# Power.net
KiCad netlist of a schematic drawn in Altium Designer
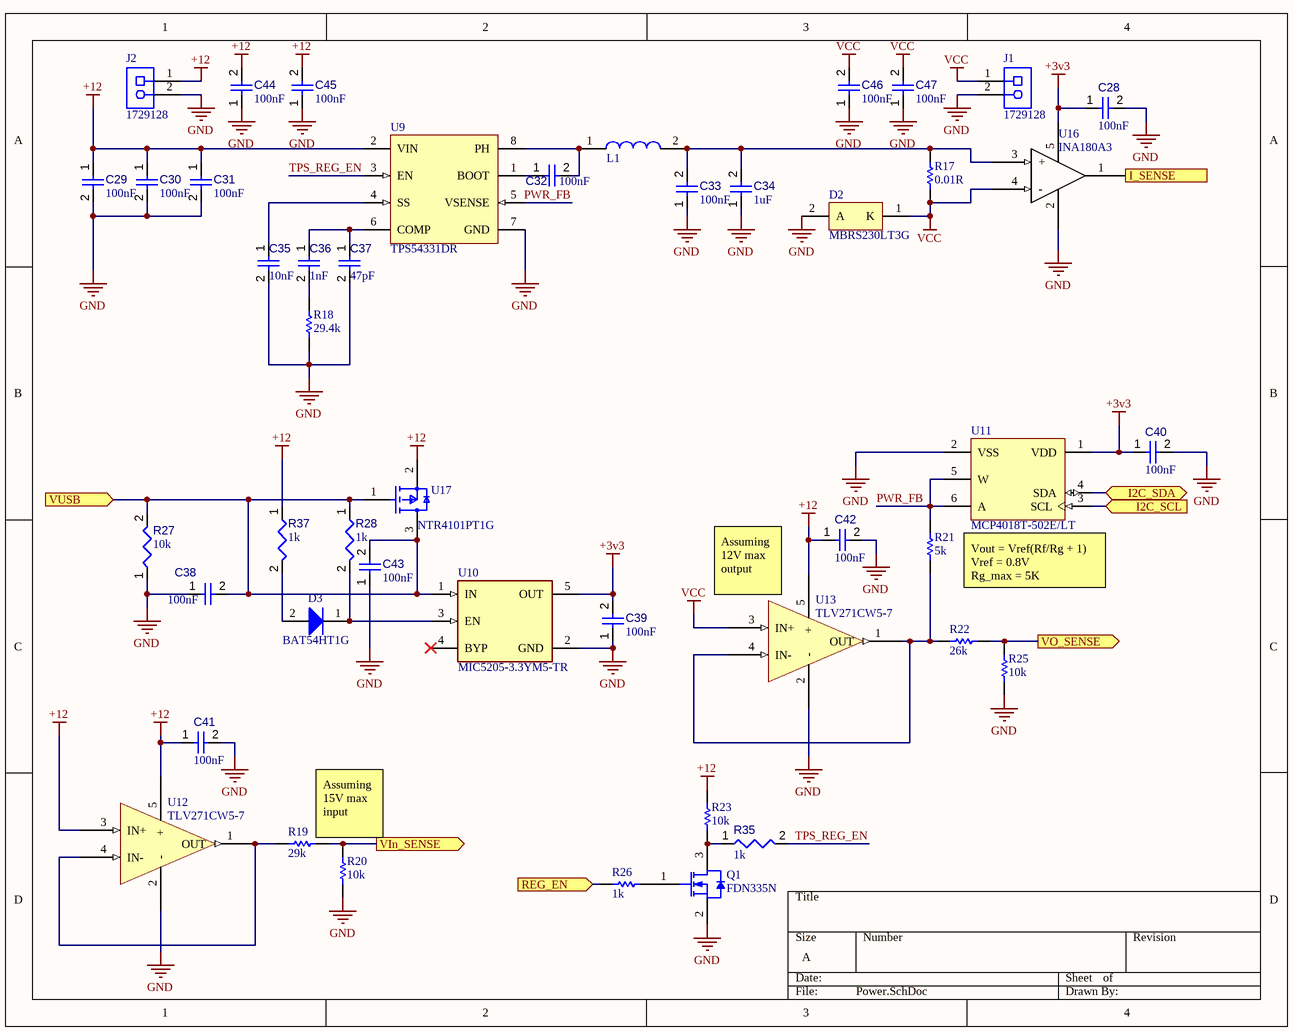
[diagram p0: Power.SchDoc]

(export (version "E")
  (design (tool "Eeschema 10.0.6"))
  (components
    (comp (ref "C28")
      (value "100nF")
      (footprint "CAPC2013X95X50ML10T25")
      (description "Chip Capacitor, 100 nF, +/- 10%, 50 V, 0805 (2012 Metric)")
      (fields (field (name "TOLERANCE") "10%") (field (name "Comment") "Capacitor 100 nF +/-10% 50 V 0805"))
      (libsource (lib "Aditya Sehgal") (part "CAP-NP-2"))
    )
    (comp (ref "C29")
      (value "100nF")
      (footprint "CAPC2013X95X50ML10T25")
      (description "Chip Capacitor, 100 nF, +/- 10%, 50 V, 0805 (2012 Metric)")
      (fields (field (name "TOLERANCE") "10%") (field (name "Comment") "Capacitor 100 nF +/-10% 50 V 0805"))
      (libsource (lib "Aditya Sehgal") (part "CAP-NP-2"))
    )
    (comp (ref "C30")
      (value "100nF")
      (footprint "CAPC2013X95X50ML10T25")
      (description "Chip Capacitor, 100 nF, +/- 10%, 50 V, 0805 (2012 Metric)")
      (fields (field (name "TOLERANCE") "10%") (field (name "Comment") "Capacitor 100 nF +/-10% 50 V 0805"))
      (libsource (lib "Aditya Sehgal") (part "CAP-NP-2"))
    )
    (comp (ref "C31")
      (value "100nF")
      (footprint "CAPC2013X95X50ML10T25")
      (description "Chip Capacitor, 100 nF, +/- 10%, 50 V, 0805 (2012 Metric)")
      (fields (field (name "TOLERANCE") "10%") (field (name "Comment") "Capacitor 100 nF +/-10% 50 V 0805"))
      (libsource (lib "Aditya Sehgal") (part "CAP-NP-2"))
    )
    (comp (ref "C32")
      (value "100nF")
      (footprint "CAPC2013X95X50ML10T25")
      (description "Chip Capacitor, 100 nF, +/- 10%, 50 V, 0805 (2012 Metric)")
      (fields (field (name "TOLERANCE") "10%") (field (name "Comment") "Capacitor 100 nF +/-10% 50 V 0805"))
      (libsource (lib "Aditya Sehgal") (part "CAP-NP-2"))
    )
    (comp (ref "C33")
      (value "100nF")
      (footprint "CAPC2013X95X50ML10T25")
      (description "Chip Capacitor, 100 nF, +/- 10%, 50 V, 0805 (2012 Metric)")
      (fields (field (name "TOLERANCE") "10%") (field (name "Comment") "Capacitor 100 nF +/-10% 50 V 0805"))
      (libsource (lib "Aditya Sehgal") (part "CAP-NP-2"))
    )
    (comp (ref "C34")
      (value "1uF")
      (footprint "CAPC2013X95X50ML10T25")
      (description "Chip Capacitor, 100 nF, +/- 10%, 50 V, 0805 (2012 Metric)")
      (fields (field (name "TOLERANCE") "10%") (field (name "Comment") "Capacitor 100 nF +/-10% 50 V 0805"))
      (libsource (lib "Aditya Sehgal") (part "CAP-NP-2"))
    )
    (comp (ref "C35")
      (value "10nF")
      (footprint "CAPC2013X95X50ML10T25")
      (description "Chip Capacitor, 100 nF, +/- 10%, 50 V, 0805 (2012 Metric)")
      (fields (field (name "TOLERANCE") "10%") (field (name "Comment") "Capacitor 100 nF +/-10% 50 V 0805"))
      (libsource (lib "Aditya Sehgal") (part "CAP-NP-2"))
    )
    (comp (ref "C36")
      (value "1nF")
      (footprint "CAPC2013X95X50ML10T25")
      (description "Chip Capacitor, 100 nF, +/- 10%, 50 V, 0805 (2012 Metric)")
      (fields (field (name "TOLERANCE") "10%") (field (name "Comment") "Capacitor 100 nF +/-10% 50 V 0805"))
      (libsource (lib "Aditya Sehgal") (part "CAP-NP-2"))
    )
    (comp (ref "C37")
      (value "47pF")
      (footprint "CAPC2013X95X50ML10T25")
      (description "Chip Capacitor, 100 nF, +/- 10%, 50 V, 0805 (2012 Metric)")
      (fields (field (name "TOLERANCE") "10%") (field (name "Comment") "Capacitor 100 nF +/-10% 50 V 0805"))
      (libsource (lib "Aditya Sehgal") (part "CAP-NP-2"))
    )
    (comp (ref "C38")
      (value "100nF")
      (footprint "CAPC2013X95X50ML10T25")
      (description "Chip Capacitor, 100 nF, +/- 10%, 50 V, 0805 (2012 Metric)")
      (fields (field (name "TOLERANCE") "10%") (field (name "Comment") "Capacitor 100 nF +/-10% 50 V 0805"))
      (libsource (lib "Aditya Sehgal") (part "CAP-NP-2"))
    )
    (comp (ref "C39")
      (value "100nF")
      (footprint "CAPC2013X95X50ML10T25")
      (description "Chip Capacitor, 100 nF, +/- 10%, 50 V, 0805 (2012 Metric)")
      (fields (field (name "TOLERANCE") "10%") (field (name "Comment") "Capacitor 100 nF +/-10% 50 V 0805"))
      (libsource (lib "Aditya Sehgal") (part "CAP-NP-2"))
    )
    (comp (ref "C40")
      (value "100nF")
      (footprint "CAPC2013X95X50ML10T25")
      (description "Chip Capacitor, 100 nF, +/- 10%, 50 V, 0805 (2012 Metric)")
      (fields (field (name "TOLERANCE") "10%") (field (name "Comment") "Capacitor 100 nF +/-10% 50 V 0805"))
      (libsource (lib "Aditya Sehgal") (part "CAP-NP-2"))
    )
    (comp (ref "C41")
      (value "100nF")
      (footprint "CAPC2013X95X50ML10T25")
      (description "Chip Capacitor, 100 nF, +/- 10%, 50 V, 0805 (2012 Metric)")
      (fields (field (name "TOLERANCE") "10%") (field (name "Comment") "Capacitor 100 nF +/-10% 50 V 0805"))
      (libsource (lib "Aditya Sehgal") (part "CAP-NP-2"))
    )
    (comp (ref "C42")
      (value "100nF")
      (footprint "CAPC2013X95X50ML10T25")
      (description "Chip Capacitor, 100 nF, +/- 10%, 50 V, 0805 (2012 Metric)")
      (fields (field (name "TOLERANCE") "10%") (field (name "Comment") "Capacitor 100 nF +/-10% 50 V 0805"))
      (libsource (lib "Aditya Sehgal") (part "CAP-NP-2"))
    )
    (comp (ref "C43")
      (value "100nF")
      (footprint "CAPC0805(2012)145_L")
      (description "Chip Capacitor, 100µF +/-20%, 6.3V, 0805, Thickness 1.45 mm")
      (fields (field (name "TOLERANCE") "10%") (field (name "Comment") "Capacitor 100µF +/-20% 6.3V 0805"))
      (libsource (lib "University of California Santa Cruz") (part "CAP-NP-2"))
    )
    (comp (ref "C44")
      (value "100nF")
      (footprint "CAPC2013X95X50LL10T25")
      (description "Chip Capacitor, 100 nF, +/- 10%, 50 V, 0805 (2012 Metric)")
      (fields (field (name "TOLERANCE") "10%") (field (name "Comment") "Capacitor 100 nF +/-10% 50 V 0805"))
      (libsource (lib "University of California Santa Cruz") (part "CAP-NP-2"))
    )
    (comp (ref "C45")
      (value "100nF")
      (footprint "CAPC2013X95X50LL10T25")
      (description "Chip Capacitor, 100 nF, +/- 10%, 50 V, 0805 (2012 Metric)")
      (fields (field (name "TOLERANCE") "10%") (field (name "Comment") "Capacitor 100 nF +/-10% 50 V 0805"))
      (libsource (lib "University of California Santa Cruz") (part "CAP-NP-2"))
    )
    (comp (ref "C46")
      (value "100nF")
      (footprint "CAPC2013X95X50LL10T25")
      (description "Chip Capacitor, 100 nF, +/- 10%, 50 V, 0805 (2012 Metric)")
      (fields (field (name "TOLERANCE") "10%") (field (name "Comment") "Capacitor 100 nF +/-10% 50 V 0805"))
      (libsource (lib "University of California Santa Cruz") (part "CAP-NP-2"))
    )
    (comp (ref "C47")
      (value "100nF")
      (footprint "CAPC2013X95X50LL10T25")
      (description "Chip Capacitor, 100 nF, +/- 10%, 50 V, 0805 (2012 Metric)")
      (fields (field (name "TOLERANCE") "10%") (field (name "Comment") "Capacitor 100 nF +/-10% 50 V 0805"))
      (libsource (lib "University of California Santa Cruz") (part "CAP-NP-2"))
    )
    (comp (ref "D2")
      (value "MBRS230LT3G")
      (footprint "ONSC-SMB-2-403A-03_D_V")
      (description "Schottky Power Rectifier, 2-Pin SMB, Pb-Free, Tape and Reel")
      (fields (field (name "MANUFACTURER") "On Semiconductor"))
      (libsource (lib "Altium Content Vault") (part "ONSC-D-K1A2-2_A"))
    )
    (comp (ref "D3")
      (value "BAT54HT1G")
      (footprint "ONSC-SOD-323-2-477-02_V")
      (description "Schottky Barrier Diode, 2-Pin SOD-323, Pb-Free, Tape and Reel")
      (fields (field (name "MANUFACTURER") "On Semiconductor"))
      (libsource (lib "Altium Content Vault") (part "ONSC-D-K1A2-2"))
    )
    (comp (ref "J1")
      (value "1729128")
      (footprint "PHOE-1729128-2_V")
      (description "PCB Terminal Block, 13.5 A, 400 V, 2-Pin THD, RoHS, Bulk")
      (fields (field (name "MANUFACTURER") "Phoenix Contact"))
      (libsource (lib "") (part "CN-2P-F-R2_1"))
    )
    (comp (ref "J2")
      (value "1729128")
      (footprint "PHOE-1729128-2_V")
      (description "PCB Terminal Block, 13.5 A, 400 V, 2-Pin THD, RoHS, Bulk")
      (fields (field (name "MANUFACTURER") "Phoenix Contact"))
      (libsource (lib "Altium Content Vault") (part "CN-2P-F-R2"))
    )
    (comp (ref "L1")
      (value "LQH5BPN4R7NT0L")
      (footprint "LQH5BPN4R7NT0L-Footprint-1")
      (description "4.7uH 2A 58mOhm 5x5mm inductor Murata")
      (libsource (lib "Aditya Sehgal") (part "LQH5BPN4R7NT0L"))
    )
    (comp (ref "Q1")
      (value "FDN335N")
      (footprint "FAIR-SSOT3L-3_V")
      (fields (field (name "MANUFACTURER") "FairchildSemiconductor"))
      (libsource (lib "Altium Content Vault") (part "NEMOS-GSD-3"))
    )
    (comp (ref "R17")
      (value "0.01R")
      (footprint "RESC3216X60X45ML15T20")
      (description "Chip Resistor, 0 Ohm, +/- 5%, 0.25 W, -55 to 155 degC, 1206 (3216 Metric)")
      (fields (field (name "POWER") "250mW") (field (name "TOLERANCE") "5%"))
      (libsource (lib "Aditya Sehgal") (part "RES-2"))
    )
    (comp (ref "R18")
      (value "29.4k")
      (footprint "RESC2013X50X35ML15T15")
      (description "Chip Resistor, 0 Ohm, +/- 1%, 125 mW, -55 to 155 degC, 0805 (2012 Metric)")
      (fields (field (name "TOLERANCE") "1%") (field (name "POWER") "125mW"))
      (libsource (lib "Aditya Sehgal") (part "RES-2"))
    )
    (comp (ref "R19")
      (value "29k")
      (footprint "RESC2013X50X35ML15T15")
      (description "Chip Resistor, 0 Ohm, +/- 1%, 125 mW, -55 to 155 degC, 0805 (2012 Metric)")
      (fields (field (name "TOLERANCE") "1%") (field (name "POWER") "125mW"))
      (libsource (lib "Aditya Sehgal") (part "RES-2"))
    )
    (comp (ref "R20")
      (value "10k")
      (footprint "RESC2013X50X35ML15T15")
      (description "Chip Resistor, 0 Ohm, +/- 1%, 125 mW, -55 to 155 degC, 0805 (2012 Metric)")
      (fields (field (name "TOLERANCE") "1%") (field (name "POWER") "125mW"))
      (libsource (lib "Aditya Sehgal") (part "RES-2"))
    )
    (comp (ref "R21")
      (value "5k")
      (footprint "RESC2013X50X35ML15T15")
      (description "Chip Resistor, 0 Ohm, +/- 1%, 125 mW, -55 to 155 degC, 0805 (2012 Metric)")
      (fields (field (name "TOLERANCE") "1%") (field (name "POWER") "125mW"))
      (libsource (lib "Aditya Sehgal") (part "RES-2"))
    )
    (comp (ref "R22")
      (value "26k")
      (footprint "RESC2013X50X35ML15T15")
      (description "Chip Resistor, 0 Ohm, +/- 1%, 125 mW, -55 to 155 degC, 0805 (2012 Metric)")
      (fields (field (name "TOLERANCE") "1%") (field (name "POWER") "125mW"))
      (libsource (lib "Aditya Sehgal") (part "RES-2"))
    )
    (comp (ref "R23")
      (value "10k")
      (footprint "RESC2013X50X35ML15T15")
      (description "Chip Resistor, 0 Ohm, +/- 1%, 125 mW, -55 to 155 degC, 0805 (2012 Metric)")
      (fields (field (name "TOLERANCE") "1%") (field (name "POWER") "125mW"))
      (libsource (lib "Aditya Sehgal") (part "RES-2"))
    )
    (comp (ref "R25")
      (value "10k")
      (footprint "RESC2013X50X35ML15T15")
      (description "Chip Resistor, 0 Ohm, +/- 1%, 125 mW, -55 to 155 degC, 0805 (2012 Metric)")
      (fields (field (name "TOLERANCE") "1%") (field (name "POWER") "125mW"))
      (libsource (lib "Aditya Sehgal") (part "RES-2"))
    )
    (comp (ref "R26")
      (value "1k")
      (footprint "RESC2013X50X35ML15T15")
      (description "Chip Resistor, 0 Ohm, +/- 1%, 125 mW, -55 to 155 degC, 0805 (2012 Metric)")
      (fields (field (name "TOLERANCE") "1%") (field (name "POWER") "125mW"))
      (libsource (lib "Aditya Sehgal") (part "RES-2"))
    )
    (comp (ref "R27")
      (value "10k")
      (footprint "RESC2013X50X35ML15T15")
      (description "Chip Resistor, 10 KOhm, +/- 1%, 125 mW, -55 to 155 degC, 0805 (2012 Metric)")
      (fields (field (name "POWER") "125mW") (field (name "TOLERANCE") "1%"))
      (libsource (lib "University of California Santa Cruz") (part "RES-2"))
    )
    (comp (ref "R28")
      (value "1k")
      (footprint "RESC2013X50X35ML15T15")
      (description "Chip Resistor, 10 KOhm, +/- 1%, 125 mW, -55 to 155 degC, 0805 (2012 Metric)")
      (fields (field (name "POWER") "125mW") (field (name "TOLERANCE") "1%"))
      (libsource (lib "University of California Santa Cruz") (part "RES-2"))
    )
    (comp (ref "R35")
      (value "1k")
      (footprint "RESC2013X50X35ML15T15")
      (description "Chip Resistor, 10 KOhm, +/- 1%, 125 mW, -55 to 155 degC, 0805 (2012 Metric)")
      (fields (field (name "POWER") "125mW") (field (name "TOLERANCE") "1%"))
      (libsource (lib "University of California Santa Cruz") (part "RES-2"))
    )
    (comp (ref "R37")
      (value "1k")
      (footprint "RESC2013X50X35ML15T15")
      (description "Chip Resistor, 10 KOhm, +/- 1%, 125 mW, -55 to 155 degC, 0805 (2012 Metric)")
      (fields (field (name "POWER") "125mW") (field (name "TOLERANCE") "1%"))
      (libsource (lib "University of California Santa Cruz") (part "RES-2"))
    )
    (comp (ref "U9")
      (value "TPS54331DR")
      (footprint "D0008A_L")
      (fields (field (name "MANUFACTURER") "Texas Instruments"))
      (libsource (lib "Altium Content Vault") (part "TI-TPS54331D8"))
    )
    (comp (ref "U10")
      (value "MIC5205-3.3YM5-TR")
      (footprint "FP-M5-IPC_C")
      (description "IC REG LINEAR 3.3V 150MA SOT23-5")
      (fields
        (field (name "MANUFACTURER") "Microchip")
        (field (name "OCTOPART") "https://octopart.com/mic5205-3.3ym5-tr-microchip-66802130")
      )
      (libsource (lib "Altium Content Vault") (part "b2bb7f462d557aec50a251fc6568b2e"))
    )
    (comp (ref "U11")
      (value "MCP4018T-502E/LT")
      (footprint "SC70-LT6_L")
      (description "7-Bit Single I2C Digital POT with Volatile Memory, 6-pin SC70, Extended Temperature, Tape and Reel")
      (libsource (lib "Altium Content Vault") (part "IN-DPOT-MCP4018-6"))
    )
    (comp (ref "U12")
      (value "TLV271CW5-7")
      (footprint "SOT95P285X130-5N")
      (description "IC OPAMP GP 3MHZ RRO SOT25")
      (libsource (lib "University of California Santa Cruz") (part "TLV271CW5-7"))
    )
    (comp (ref "U13")
      (value "TLV271CW5-7")
      (footprint "SOT95P285X130-5N")
      (description "IC OPAMP GP 3MHZ RRO SOT25")
      (libsource (lib "University of California Santa Cruz") (part "TLV271CW5-7"))
    )
    (comp (ref "U16")
      (value "INA180A3")
      (footprint "SOT95P245X110-5N")
      (description "Current Sense Amplifier 100V/V")
      (libsource (lib "Aditya Sehgal") (part "INA180A3"))
    )
    (comp (ref "U17")
      (value "NTR4101PT1G")
      (footprint "FP-318-08-MFG")
      (description "MOSFET P-CH 20V 1.8A SOT-23")
      (libsource (lib "Altium Content Vault") (part "d54a8bb486e18a944bb8606ec07e2b8"))
    )
  )
  (nets
    (net (code "1") (name "+3v3") (class "Default")
      (node (ref "C28") (pin "1") (pinfunction "1_1") (pintype "passive"))
      (node (ref "C39") (pin "2") (pinfunction "2_2") (pintype "passive"))
      (node (ref "C40") (pin "1") (pinfunction "1_1") (pintype "passive"))
      (node (ref "U10") (pin "5") (pinfunction "OUT_5") (pintype "power_in"))
      (node (ref "U11") (pin "1") (pinfunction "VDD_1") (pintype "power_in"))
      (node (ref "U16") (pin "5") (pinfunction "Vcc_5") (pintype "passive"))
    )
    (net (code "2") (name "+12") (class "Default")
      (node (ref "C29") (pin "1") (pinfunction "1_1") (pintype "passive"))
      (node (ref "C30") (pin "1") (pinfunction "1_1") (pintype "passive"))
      (node (ref "C31") (pin "1") (pinfunction "1_1") (pintype "passive"))
      (node (ref "C41") (pin "1") (pinfunction "1_1") (pintype "passive"))
      (node (ref "C42") (pin "1") (pinfunction "1_1") (pintype "passive"))
      (node (ref "C44") (pin "2") (pinfunction "2_2") (pintype "passive"))
      (node (ref "C45") (pin "2") (pinfunction "2_2") (pintype "passive"))
      (node (ref "J2") (pin "1") (pinfunction "1_1") (pintype "passive"))
      (node (ref "R23") (pin "2") (pinfunction "2_2") (pintype "passive"))
      (node (ref "R37") (pin "1") (pinfunction "1_1") (pintype "passive"))
      (node (ref "U12") (pin "3") (pinfunction "IN+_3") (pintype "input"))
      (node (ref "U12") (pin "5") (pinfunction "+_5") (pintype "power_in"))
      (node (ref "U13") (pin "5") (pinfunction "+_5") (pintype "power_in"))
      (node (ref "U17") (pin "2") (pinfunction "Source_2") (pintype "passive"))
      (node (ref "U9") (pin "2") (pinfunction "VIN_2") (pintype "power_in"))
    )
    (net (code "3") (name "/I2C_SCL") (class "Default")
      (node (ref "U11") (pin "3") (pinfunction "SCL_3") (pintype "input"))
    )
    (net (code "4") (name "/I2C_SDA") (class "Default")
      (node (ref "U11") (pin "4") (pinfunction "SDA_4") (pintype "bidirectional"))
    )
    (net (code "5") (name "/I_SENSE") (class "Default")
      (node (ref "U16") (pin "1") (pinfunction "out_1") (pintype "passive"))
    )
    (net (code "6") (name "/PWR_FB") (class "Default")
      (node (ref "R21") (pin "2") (pinfunction "2_2") (pintype "passive"))
      (node (ref "U11") (pin "5") (pinfunction "W_5") (pintype "passive"))
      (node (ref "U11") (pin "6") (pinfunction "A_6") (pintype "passive"))
      (node (ref "U9") (pin "5") (pinfunction "VSENSE_5") (pintype "input"))
    )
    (net (code "7") (name "/REG_EN") (class "Default")
      (node (ref "R26") (pin "1") (pinfunction "1_1") (pintype "passive"))
    )
    (net (code "8") (name "/TPS_REG_EN") (class "Default")
      (node (ref "R35") (pin "2") (pinfunction "2_2") (pintype "passive"))
      (node (ref "U9") (pin "3") (pinfunction "EN_3") (pintype "input"))
    )
    (net (code "9") (name "/VIn_SENSE") (class "Default")
      (node (ref "R19") (pin "2") (pinfunction "2_2") (pintype "passive"))
      (node (ref "R20") (pin "2") (pinfunction "2_2") (pintype "passive"))
    )
    (net (code "10") (name "/VO_SENSE") (class "Default")
      (node (ref "R22") (pin "2") (pinfunction "2_2") (pintype "passive"))
      (node (ref "R25") (pin "2") (pinfunction "2_2") (pintype "passive"))
    )
    (net (code "11") (name "/VUSB") (class "Default")
      (node (ref "C38") (pin "2") (pinfunction "2_2") (pintype "passive"))
      (node (ref "C43") (pin "2") (pinfunction "2_2") (pintype "passive"))
      (node (ref "R27") (pin "2") (pinfunction "2_2") (pintype "passive"))
      (node (ref "R28") (pin "1") (pinfunction "1_1") (pintype "passive"))
      (node (ref "U10") (pin "1") (pinfunction "IN_1") (pintype "input"))
      (node (ref "U17") (pin "1") (pinfunction "Gate_1") (pintype "passive"))
      (node (ref "U17") (pin "3") (pinfunction "Drain_3") (pintype "passive"))
    )
    (net (code "12") (name "GND") (class "Default")
      (node (ref "C28") (pin "2") (pinfunction "2_2") (pintype "passive"))
      (node (ref "C29") (pin "2") (pinfunction "2_2") (pintype "passive"))
      (node (ref "C30") (pin "2") (pinfunction "2_2") (pintype "passive"))
      (node (ref "C31") (pin "2") (pinfunction "2_2") (pintype "passive"))
      (node (ref "C33") (pin "1") (pinfunction "1_1") (pintype "passive"))
      (node (ref "C34") (pin "1") (pinfunction "1_1") (pintype "passive"))
      (node (ref "C35") (pin "2") (pinfunction "2_2") (pintype "passive"))
      (node (ref "C37") (pin "2") (pinfunction "2_2") (pintype "passive"))
      (node (ref "C38") (pin "1") (pinfunction "1_1") (pintype "passive"))
      (node (ref "C39") (pin "1") (pinfunction "1_1") (pintype "passive"))
      (node (ref "C40") (pin "2") (pinfunction "2_2") (pintype "passive"))
      (node (ref "C41") (pin "2") (pinfunction "2_2") (pintype "passive"))
      (node (ref "C42") (pin "2") (pinfunction "2_2") (pintype "passive"))
      (node (ref "C43") (pin "1") (pinfunction "1_1") (pintype "passive"))
      (node (ref "C44") (pin "1") (pinfunction "1_1") (pintype "passive"))
      (node (ref "C45") (pin "1") (pinfunction "1_1") (pintype "passive"))
      (node (ref "C46") (pin "1") (pinfunction "1_1") (pintype "passive"))
      (node (ref "C47") (pin "1") (pinfunction "1_1") (pintype "passive"))
      (node (ref "D2") (pin "2") (pinfunction "A_2") (pintype "passive"))
      (node (ref "J1") (pin "2") (pinfunction "2_2") (pintype "passive"))
      (node (ref "J2") (pin "2") (pinfunction "2_2") (pintype "passive"))
      (node (ref "Q1") (pin "2") (pinfunction "S_2") (pintype "passive"))
      (node (ref "R18") (pin "2") (pinfunction "2_2") (pintype "passive"))
      (node (ref "R20") (pin "1") (pinfunction "1_1") (pintype "passive"))
      (node (ref "R25") (pin "1") (pinfunction "1_1") (pintype "passive"))
      (node (ref "R27") (pin "1") (pinfunction "1_1") (pintype "passive"))
      (node (ref "U10") (pin "2") (pinfunction "GND_2") (pintype "power_in"))
      (node (ref "U11") (pin "2") (pinfunction "VSS_2") (pintype "power_in"))
      (node (ref "U12") (pin "2") (pinfunction "-_2") (pintype "power_in"))
      (node (ref "U13") (pin "2") (pinfunction "-_2") (pintype "power_in"))
      (node (ref "U16") (pin "2") (pinfunction "GND_2") (pintype "power_in"))
      (node (ref "U9") (pin "7") (pinfunction "GND_7") (pintype "power_in"))
    )
    (net (code "13") (name "Net-(C36-Pad2)") (class "Default")
      (node (ref "C36") (pin "2") (pinfunction "2_2") (pintype "passive"))
      (node (ref "R18") (pin "1") (pinfunction "1_1") (pintype "passive"))
    )
    (net (code "14") (name "Net-(D3-A)") (class "Default")
      (node (ref "D3") (pin "2") (pinfunction "A_2") (pintype "passive"))
      (node (ref "R37") (pin "2") (pinfunction "2_2") (pintype "passive"))
    )
    (net (code "15") (name "Net-(D3-K)") (class "Default")
      (node (ref "D3") (pin "1") (pinfunction "K_1") (pintype "passive"))
      (node (ref "R28") (pin "2") (pinfunction "2_2") (pintype "passive"))
      (node (ref "U10") (pin "3") (pinfunction "EN_3") (pintype "input"))
    )
    (net (code "16") (name "Net-(L1-7)") (class "Default")
      (node (ref "C32") (pin "2") (pinfunction "2_2") (pintype "passive"))
      (node (ref "L1") (pin "1") (pinfunction "7_1") (pintype "passive"))
      (node (ref "U9") (pin "8") (pinfunction "PH_8") (pintype "power_in"))
    )
    (net (code "17") (name "Net-(L1-8)") (class "Default")
      (node (ref "C33") (pin "2") (pinfunction "2_2") (pintype "passive"))
      (node (ref "C34") (pin "2") (pinfunction "2_2") (pintype "passive"))
      (node (ref "L1") (pin "2") (pinfunction "8_2") (pintype "passive"))
      (node (ref "R17") (pin "2") (pinfunction "2_2") (pintype "passive"))
      (node (ref "U16") (pin "3") (pinfunction "+_3") (pintype "input"))
    )
    (net (code "18") (name "Net-(Q1-D)") (class "Default")
      (node (ref "Q1") (pin "3") (pinfunction "D_3") (pintype "passive"))
      (node (ref "R23") (pin "1") (pinfunction "1_1") (pintype "passive"))
      (node (ref "R35") (pin "1") (pinfunction "1_1") (pintype "passive"))
    )
    (net (code "19") (name "Net-(Q1-G)") (class "Default")
      (node (ref "Q1") (pin "1") (pinfunction "G_1") (pintype "passive"))
      (node (ref "R26") (pin "2") (pinfunction "2_2") (pintype "passive"))
    )
    (net (code "20") (name "Net-(U9-BOOT)") (class "Default")
      (node (ref "C32") (pin "1") (pinfunction "1_1") (pintype "passive"))
      (node (ref "U9") (pin "1") (pinfunction "BOOT_1") (pintype "passive"))
    )
    (net (code "21") (name "Net-(U9-COMP)") (class "Default")
      (node (ref "C36") (pin "1") (pinfunction "1_1") (pintype "passive"))
      (node (ref "C37") (pin "1") (pinfunction "1_1") (pintype "passive"))
      (node (ref "U9") (pin "6") (pinfunction "COMP_6") (pintype "passive"))
    )
    (net (code "22") (name "Net-(U9-SS)") (class "Default")
      (node (ref "C35") (pin "1") (pinfunction "1_1") (pintype "passive"))
      (node (ref "U9") (pin "4") (pinfunction "SS_4") (pintype "input"))
    )
    (net (code "23") (name "Net-(U12-IN-)") (class "Default")
      (node (ref "R19") (pin "1") (pinfunction "1_1") (pintype "passive"))
      (node (ref "U12") (pin "1") (pinfunction "OUT_1") (pintype "output"))
      (node (ref "U12") (pin "4") (pinfunction "IN-_4") (pintype "input"))
    )
    (net (code "24") (name "Net-(U13-IN-)") (class "Default")
      (node (ref "R21") (pin "1") (pinfunction "1_1") (pintype "passive"))
      (node (ref "R22") (pin "1") (pinfunction "1_1") (pintype "passive"))
      (node (ref "U13") (pin "1") (pinfunction "OUT_1") (pintype "output"))
      (node (ref "U13") (pin "4") (pinfunction "IN-_4") (pintype "input"))
    )
    (net (code "25") (name "VCC") (class "Default")
      (node (ref "C46") (pin "2") (pinfunction "2_2") (pintype "passive"))
      (node (ref "C47") (pin "2") (pinfunction "2_2") (pintype "passive"))
      (node (ref "D2") (pin "1") (pinfunction "K_1") (pintype "passive"))
      (node (ref "J1") (pin "1") (pinfunction "1_1") (pintype "passive"))
      (node (ref "R17") (pin "1") (pinfunction "1_1") (pintype "passive"))
      (node (ref "U13") (pin "3") (pinfunction "IN+_3") (pintype "input"))
      (node (ref "U16") (pin "4") (pinfunction "-_4") (pintype "input"))
    )
    (net (code "26") (name "unconnected-(U10-BYP-Pad4)") (class "Default")
      (node (ref "U10") (pin "4") (pinfunction "BYP_4") (pintype "passive+no_connect"))
    )
  )
)
